# Memory_Address_Register.net
KiCad netlist of a schematic drawn in Altium Designer
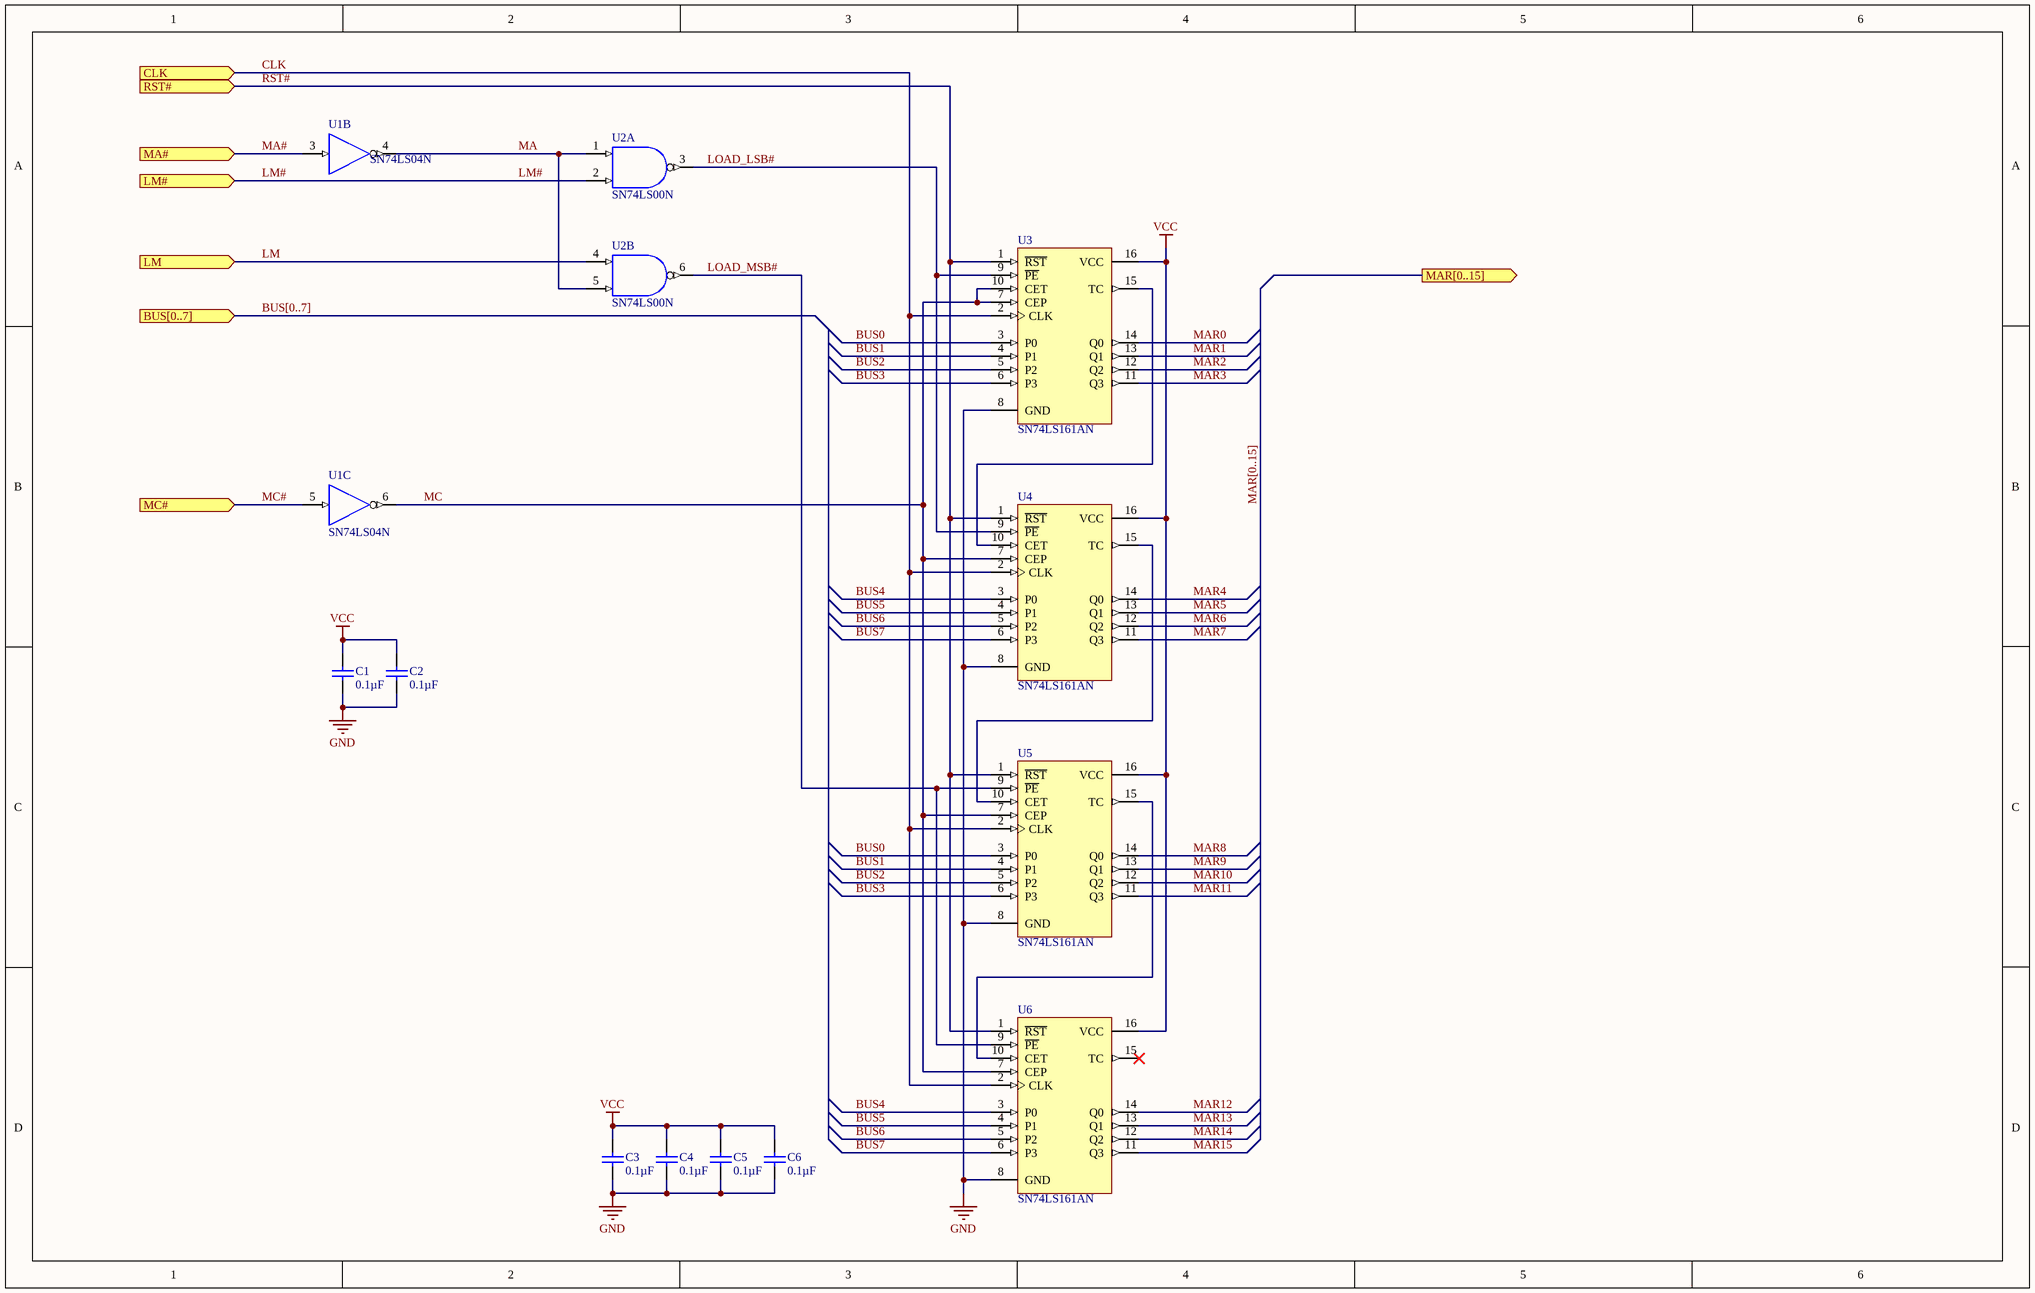
[diagram p0: Memory Address Register.SchDoc]

(export (version "E")
  (design (tool "Eeschema 10.0.6"))
  (components
    (comp (ref "C1")
      (value "K104K15X7RF5TL2")
      (footprint "VISH-K104K15X7RF5TL2")
      (description "Ceramic Capacitor, 100 nF, +/- 10%, 50 V, -55 to 125 degC, 2-Pin THD, RoHS, Tape and Reel")
      (fields
        (field (name "MANUFACTURER") "Vishay")
        (field (name "TOLERANCE") "±10%")
        (field (name "CAPACITANCE") "0.1µF")
      )
      (libsource (lib "Altium Content Vault") (part "CAP-NP-2"))
    )
    (comp (ref "C2")
      (value "K104K15X7RF5TL2")
      (footprint "VISH-K104K15X7RF5TL2")
      (description "Ceramic Capacitor, 100 nF, +/- 10%, 50 V, -55 to 125 degC, 2-Pin THD, RoHS, Tape and Reel")
      (fields
        (field (name "MANUFACTURER") "Vishay")
        (field (name "TOLERANCE") "±10%")
        (field (name "CAPACITANCE") "0.1µF")
      )
      (libsource (lib "Altium Content Vault") (part "CAP-NP-2"))
    )
    (comp (ref "C3")
      (value "K104K15X7RF5TL2")
      (footprint "VISH-K104K15X7RF5TL2")
      (description "Ceramic Capacitor, 100 nF, +/- 10%, 50 V, -55 to 125 degC, 2-Pin THD, RoHS, Tape and Reel")
      (fields
        (field (name "MANUFACTURER") "Vishay")
        (field (name "TOLERANCE") "±10%")
        (field (name "CAPACITANCE") "0.1µF")
      )
      (libsource (lib "Altium Content Vault") (part "CAP-NP-2"))
    )
    (comp (ref "C4")
      (value "K104K15X7RF5TL2")
      (footprint "VISH-K104K15X7RF5TL2")
      (description "Ceramic Capacitor, 100 nF, +/- 10%, 50 V, -55 to 125 degC, 2-Pin THD, RoHS, Tape and Reel")
      (fields
        (field (name "MANUFACTURER") "Vishay")
        (field (name "TOLERANCE") "±10%")
        (field (name "CAPACITANCE") "0.1µF")
      )
      (libsource (lib "Altium Content Vault") (part "CAP-NP-2"))
    )
    (comp (ref "C5")
      (value "K104K15X7RF5TL2")
      (footprint "VISH-K104K15X7RF5TL2")
      (description "Ceramic Capacitor, 100 nF, +/- 10%, 50 V, -55 to 125 degC, 2-Pin THD, RoHS, Tape and Reel")
      (fields
        (field (name "MANUFACTURER") "Vishay")
        (field (name "TOLERANCE") "±10%")
        (field (name "CAPACITANCE") "0.1µF")
      )
      (libsource (lib "Altium Content Vault") (part "CAP-NP-2"))
    )
    (comp (ref "C6")
      (value "K104K15X7RF5TL2")
      (footprint "VISH-K104K15X7RF5TL2")
      (description "Ceramic Capacitor, 100 nF, +/- 10%, 50 V, -55 to 125 degC, 2-Pin THD, RoHS, Tape and Reel")
      (fields
        (field (name "MANUFACTURER") "Vishay")
        (field (name "TOLERANCE") "±10%")
        (field (name "CAPACITANCE") "0.1µF")
      )
      (libsource (lib "Altium Content Vault") (part "CAP-NP-2"))
    )
    (comp (ref "U1")
      (value "SN74LS04N")
      (footprint "N014")
      (description "Hex Inverter")
      (fields (field (name "PUBLISHER") "Altium Limited"))
      (libsource (lib "TI Logic Gate 2") (part "SN74LS04N"))
    )
    (comp (ref "U2")
      (value "SN74LS00N")
      (footprint "N014")
      (description "Quadruple 2-Input Positive-NAND Gate")
      (fields (field (name "PUBLISHER") "Altium Limited"))
      (libsource (lib "TI Logic Gate 2") (part "SN74LS00N"))
    )
    (comp (ref "U3")
      (value "SN74LS161AN")
      (footprint "N016")
      (description "Synchronous 4-Bit Counter")
      (fields (field (name "PUBLISHER") "Altium Limited"))
      (libsource (lib "TI Logic Counter") (part "SN74LS161AN"))
    )
    (comp (ref "U4")
      (value "SN74LS161AN")
      (footprint "N016")
      (description "Synchronous 4-Bit Counter")
      (fields (field (name "PUBLISHER") "Altium Limited"))
      (libsource (lib "TI Logic Counter") (part "SN74LS161AN"))
    )
    (comp (ref "U5")
      (value "SN74LS161AN")
      (footprint "N016")
      (description "Synchronous 4-Bit Counter")
      (fields (field (name "PUBLISHER") "Altium Limited"))
      (libsource (lib "TI Logic Counter") (part "SN74LS161AN"))
    )
    (comp (ref "U6")
      (value "SN74LS161AN")
      (footprint "N016")
      (description "Synchronous 4-Bit Counter")
      (fields (field (name "PUBLISHER") "Altium Limited"))
      (libsource (lib "TI Logic Counter") (part "SN74LS161AN"))
    )
  )
  (nets
    (net (code "1") (name "/BUS0") (class "Default")
      (node (ref "U3") (pin "3") (pinfunction "P0_3") (pintype "input"))
      (node (ref "U5") (pin "3") (pinfunction "P0_3") (pintype "input"))
    )
    (net (code "2") (name "/BUS1") (class "Default")
      (node (ref "U3") (pin "4") (pinfunction "P1_4") (pintype "input"))
      (node (ref "U5") (pin "4") (pinfunction "P1_4") (pintype "input"))
    )
    (net (code "3") (name "/BUS2") (class "Default")
      (node (ref "U3") (pin "5") (pinfunction "P2_5") (pintype "input"))
      (node (ref "U5") (pin "5") (pinfunction "P2_5") (pintype "input"))
    )
    (net (code "4") (name "/BUS3") (class "Default")
      (node (ref "U3") (pin "6") (pinfunction "P3_6") (pintype "input"))
      (node (ref "U5") (pin "6") (pinfunction "P3_6") (pintype "input"))
    )
    (net (code "5") (name "/BUS4") (class "Default")
      (node (ref "U4") (pin "3") (pinfunction "P0_3") (pintype "input"))
      (node (ref "U6") (pin "3") (pinfunction "P0_3") (pintype "input"))
    )
    (net (code "6") (name "/BUS5") (class "Default")
      (node (ref "U4") (pin "4") (pinfunction "P1_4") (pintype "input"))
      (node (ref "U6") (pin "4") (pinfunction "P1_4") (pintype "input"))
    )
    (net (code "7") (name "/BUS6") (class "Default")
      (node (ref "U4") (pin "5") (pinfunction "P2_5") (pintype "input"))
      (node (ref "U6") (pin "5") (pinfunction "P2_5") (pintype "input"))
    )
    (net (code "8") (name "/BUS7") (class "Default")
      (node (ref "U4") (pin "6") (pinfunction "P3_6") (pintype "input"))
      (node (ref "U6") (pin "6") (pinfunction "P3_6") (pintype "input"))
    )
    (net (code "10") (name "/CLK") (class "Default")
      (node (ref "U3") (pin "2") (pinfunction "CLK_2") (pintype "input"))
      (node (ref "U4") (pin "2") (pinfunction "CLK_2") (pintype "input"))
      (node (ref "U5") (pin "2") (pinfunction "CLK_2") (pintype "input"))
      (node (ref "U6") (pin "2") (pinfunction "CLK_2") (pintype "input"))
    )
    (net (code "11") (name "/LM") (class "Default")
      (node (ref "U2") (pin "4") (pinfunction "A_4") (pintype "input"))
    )
    (net (code "12") (name "/LM#") (class "Default")
      (node (ref "U2") (pin "2") (pinfunction "B_2") (pintype "input"))
    )
    (net (code "13") (name "/LOAD_LSB#") (class "Default")
      (node (ref "U2") (pin "3") (pinfunction "Y_3") (pintype "output"))
      (node (ref "U3") (pin "9") (pinfunction "~{PE}_9") (pintype "input"))
      (node (ref "U4") (pin "9") (pinfunction "~{PE}_9") (pintype "input"))
    )
    (net (code "14") (name "/LOAD_MSB#") (class "Default")
      (node (ref "U2") (pin "6") (pinfunction "Y_6") (pintype "output"))
      (node (ref "U5") (pin "9") (pinfunction "~{PE}_9") (pintype "input"))
      (node (ref "U6") (pin "9") (pinfunction "~{PE}_9") (pintype "input"))
    )
    (net (code "15") (name "/MA") (class "Default")
      (node (ref "U1") (pin "4") (pinfunction "Y_4") (pintype "output"))
      (node (ref "U2") (pin "1") (pinfunction "A_1") (pintype "input"))
      (node (ref "U2") (pin "5") (pinfunction "B_5") (pintype "input"))
    )
    (net (code "16") (name "/MA#") (class "Default")
      (node (ref "U1") (pin "3") (pinfunction "A_3") (pintype "input"))
    )
    (net (code "17") (name "/MAR0") (class "Default")
      (node (ref "U3") (pin "14") (pinfunction "Q0_14") (pintype "output"))
    )
    (net (code "18") (name "/MAR1") (class "Default")
      (node (ref "U3") (pin "13") (pinfunction "Q1_13") (pintype "output"))
    )
    (net (code "19") (name "/MAR2") (class "Default")
      (node (ref "U3") (pin "12") (pinfunction "Q2_12") (pintype "output"))
    )
    (net (code "20") (name "/MAR3") (class "Default")
      (node (ref "U3") (pin "11") (pinfunction "Q3_11") (pintype "output"))
    )
    (net (code "21") (name "/MAR4") (class "Default")
      (node (ref "U4") (pin "14") (pinfunction "Q0_14") (pintype "output"))
    )
    (net (code "22") (name "/MAR5") (class "Default")
      (node (ref "U4") (pin "13") (pinfunction "Q1_13") (pintype "output"))
    )
    (net (code "23") (name "/MAR6") (class "Default")
      (node (ref "U4") (pin "12") (pinfunction "Q2_12") (pintype "output"))
    )
    (net (code "24") (name "/MAR7") (class "Default")
      (node (ref "U4") (pin "11") (pinfunction "Q3_11") (pintype "output"))
    )
    (net (code "25") (name "/MAR8") (class "Default")
      (node (ref "U5") (pin "14") (pinfunction "Q0_14") (pintype "output"))
    )
    (net (code "26") (name "/MAR9") (class "Default")
      (node (ref "U5") (pin "13") (pinfunction "Q1_13") (pintype "output"))
    )
    (net (code "27") (name "/MAR10") (class "Default")
      (node (ref "U5") (pin "12") (pinfunction "Q2_12") (pintype "output"))
    )
    (net (code "28") (name "/MAR11") (class "Default")
      (node (ref "U5") (pin "11") (pinfunction "Q3_11") (pintype "output"))
    )
    (net (code "29") (name "/MAR12") (class "Default")
      (node (ref "U6") (pin "14") (pinfunction "Q0_14") (pintype "output"))
    )
    (net (code "30") (name "/MAR13") (class "Default")
      (node (ref "U6") (pin "13") (pinfunction "Q1_13") (pintype "output"))
    )
    (net (code "31") (name "/MAR14") (class "Default")
      (node (ref "U6") (pin "12") (pinfunction "Q2_12") (pintype "output"))
    )
    (net (code "32") (name "/MAR15") (class "Default")
      (node (ref "U6") (pin "11") (pinfunction "Q3_11") (pintype "output"))
    )
    (net (code "34") (name "/MC") (class "Default")
      (node (ref "U1") (pin "6") (pinfunction "Y_6") (pintype "output"))
      (node (ref "U3") (pin "10") (pinfunction "CET_10") (pintype "input"))
      (node (ref "U3") (pin "7") (pinfunction "CEP_7") (pintype "input"))
      (node (ref "U4") (pin "7") (pinfunction "CEP_7") (pintype "input"))
      (node (ref "U5") (pin "7") (pinfunction "CEP_7") (pintype "input"))
      (node (ref "U6") (pin "7") (pinfunction "CEP_7") (pintype "input"))
    )
    (net (code "35") (name "/MC#") (class "Default")
      (node (ref "U1") (pin "5") (pinfunction "A_5") (pintype "input"))
    )
    (net (code "36") (name "/RST#") (class "Default")
      (node (ref "U3") (pin "1") (pinfunction "~{RST}_1") (pintype "input"))
      (node (ref "U4") (pin "1") (pinfunction "~{RST}_1") (pintype "input"))
      (node (ref "U5") (pin "1") (pinfunction "~{RST}_1") (pintype "input"))
      (node (ref "U6") (pin "1") (pinfunction "~{RST}_1") (pintype "input"))
    )
    (net (code "37") (name "GND") (class "Default")
      (node (ref "C1") (pin "2") (pinfunction "2_2") (pintype "passive"))
      (node (ref "C2") (pin "2") (pinfunction "2_2") (pintype "passive"))
      (node (ref "C3") (pin "2") (pinfunction "2_2") (pintype "passive"))
      (node (ref "C4") (pin "2") (pinfunction "2_2") (pintype "passive"))
      (node (ref "C5") (pin "2") (pinfunction "2_2") (pintype "passive"))
      (node (ref "C6") (pin "2") (pinfunction "2_2") (pintype "passive"))
      (node (ref "U1") (pin "7") (pinfunction "GND_7") (pintype "power_in"))
      (node (ref "U2") (pin "7") (pinfunction "GND_7") (pintype "power_in"))
      (node (ref "U3") (pin "8") (pinfunction "GND_8") (pintype "power_in"))
      (node (ref "U4") (pin "8") (pinfunction "GND_8") (pintype "power_in"))
      (node (ref "U5") (pin "8") (pinfunction "GND_8") (pintype "power_in"))
      (node (ref "U6") (pin "8") (pinfunction "GND_8") (pintype "power_in"))
    )
    (net (code "38") (name "Net-(U3-TC)") (class "Default")
      (node (ref "U3") (pin "15") (pinfunction "TC_15") (pintype "output"))
      (node (ref "U4") (pin "10") (pinfunction "CET_10") (pintype "input"))
    )
    (net (code "39") (name "Net-(U4-TC)") (class "Default")
      (node (ref "U4") (pin "15") (pinfunction "TC_15") (pintype "output"))
      (node (ref "U5") (pin "10") (pinfunction "CET_10") (pintype "input"))
    )
    (net (code "40") (name "Net-(U5-TC)") (class "Default")
      (node (ref "U5") (pin "15") (pinfunction "TC_15") (pintype "output"))
      (node (ref "U6") (pin "10") (pinfunction "CET_10") (pintype "input"))
    )
    (net (code "41") (name "VCC") (class "Default")
      (node (ref "C1") (pin "1") (pinfunction "1_1") (pintype "passive"))
      (node (ref "C2") (pin "1") (pinfunction "1_1") (pintype "passive"))
      (node (ref "C3") (pin "1") (pinfunction "1_1") (pintype "passive"))
      (node (ref "C4") (pin "1") (pinfunction "1_1") (pintype "passive"))
      (node (ref "C5") (pin "1") (pinfunction "1_1") (pintype "passive"))
      (node (ref "C6") (pin "1") (pinfunction "1_1") (pintype "passive"))
      (node (ref "U1") (pin "14") (pinfunction "VCC_14") (pintype "power_in"))
      (node (ref "U2") (pin "14") (pinfunction "VCC_14") (pintype "power_in"))
      (node (ref "U3") (pin "16") (pinfunction "VCC_16") (pintype "power_in"))
      (node (ref "U4") (pin "16") (pinfunction "VCC_16") (pintype "power_in"))
      (node (ref "U5") (pin "16") (pinfunction "VCC_16") (pintype "power_in"))
      (node (ref "U6") (pin "16") (pinfunction "VCC_16") (pintype "power_in"))
    )
    (net (code "42") (name "unconnected-(U6-TC-Pad15)") (class "Default")
      (node (ref "U6") (pin "15") (pinfunction "TC_15") (pintype "output+no_connect"))
    )
  )
)
